# electronics_board.net
KiCad netlist of a schematic drawn in EAGLE
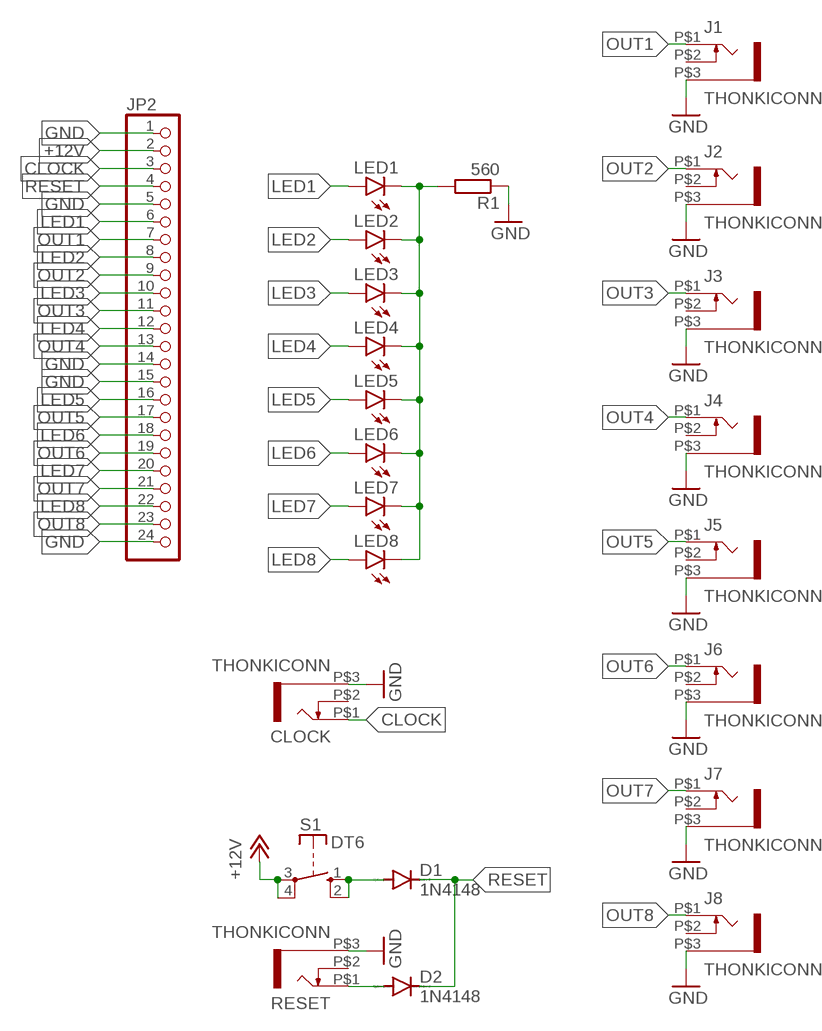
[diagram p0: schematic, sheet 1]

(export (version "E")
  (design (tool "Eeschema 10.0.6"))
  (components
    (comp (ref "CLOCK")
      (value "THONKICONN")
      (footprint "eagle-import:WQP-PJ301M-12_JACK")
      (libsource (lib "eagle-import") (part "WQP-PJ301M-12_JACK"))
    )
    (comp (ref "D1")
      (value "1N4148")
      (footprint "eagle-import:DO35-7")
      (libsource (lib "eagle-import") (part "1N4148DO35-7"))
    )
    (comp (ref "D2")
      (value "1N4148")
      (footprint "eagle-import:DO35-7")
      (libsource (lib "eagle-import") (part "1N4148DO35-7"))
    )
    (comp (ref "J1")
      (value "THONKICONN")
      (footprint "eagle-import:WQP-PJ301M-12_JACK")
      (libsource (lib "eagle-import") (part "WQP-PJ301M-12_JACK"))
    )
    (comp (ref "J2")
      (value "THONKICONN")
      (footprint "eagle-import:WQP-PJ301M-12_JACK")
      (libsource (lib "eagle-import") (part "WQP-PJ301M-12_JACK"))
    )
    (comp (ref "J3")
      (value "THONKICONN")
      (footprint "eagle-import:WQP-PJ301M-12_JACK")
      (libsource (lib "eagle-import") (part "WQP-PJ301M-12_JACK"))
    )
    (comp (ref "J4")
      (value "THONKICONN")
      (footprint "eagle-import:WQP-PJ301M-12_JACK")
      (libsource (lib "eagle-import") (part "WQP-PJ301M-12_JACK"))
    )
    (comp (ref "J5")
      (value "THONKICONN")
      (footprint "eagle-import:WQP-PJ301M-12_JACK")
      (libsource (lib "eagle-import") (part "WQP-PJ301M-12_JACK"))
    )
    (comp (ref "J6")
      (value "THONKICONN")
      (footprint "eagle-import:WQP-PJ301M-12_JACK")
      (libsource (lib "eagle-import") (part "WQP-PJ301M-12_JACK"))
    )
    (comp (ref "J7")
      (value "THONKICONN")
      (footprint "eagle-import:WQP-PJ301M-12_JACK")
      (libsource (lib "eagle-import") (part "WQP-PJ301M-12_JACK"))
    )
    (comp (ref "J8")
      (value "THONKICONN")
      (footprint "eagle-import:WQP-PJ301M-12_JACK")
      (libsource (lib "eagle-import") (part "WQP-PJ301M-12_JACK"))
    )
    (comp (ref "JP2")
      (value "PINHD-1X24")
      (footprint "eagle-import:1X24")
      (libsource (lib "eagle-import") (part "PINHD-1X24"))
    )
    (comp (ref "LED1")
      (value "LED")
      (footprint "eagle-import:LED_3MM")
      (fields (field (name "MF") "BROADCOM") (field (name "MPN") "HLMP-1700"))
      (libsource (lib "eagle-import") (part "LED"))
    )
    (comp (ref "LED2")
      (value "LED")
      (footprint "eagle-import:LED_3MM")
      (fields (field (name "MF") "BROADCOM") (field (name "MPN") "HLMP-1700"))
      (libsource (lib "eagle-import") (part "LED"))
    )
    (comp (ref "LED3")
      (value "LED")
      (footprint "eagle-import:LED_3MM")
      (fields (field (name "MF") "BROADCOM") (field (name "MPN") "HLMP-1700"))
      (libsource (lib "eagle-import") (part "LED"))
    )
    (comp (ref "LED4")
      (value "LED")
      (footprint "eagle-import:LED_3MM")
      (fields (field (name "MF") "BROADCOM") (field (name "MPN") "HLMP-1700"))
      (libsource (lib "eagle-import") (part "LED"))
    )
    (comp (ref "LED5")
      (value "LED")
      (footprint "eagle-import:LED_3MM")
      (fields (field (name "MF") "BROADCOM") (field (name "MPN") "HLMP-1700"))
      (libsource (lib "eagle-import") (part "LED"))
    )
    (comp (ref "LED6")
      (value "LED")
      (footprint "eagle-import:LED_3MM")
      (fields (field (name "MF") "BROADCOM") (field (name "MPN") "HLMP-1700"))
      (libsource (lib "eagle-import") (part "LED"))
    )
    (comp (ref "LED7")
      (value "LED")
      (footprint "eagle-import:LED_3MM")
      (fields (field (name "MF") "BROADCOM") (field (name "MPN") "HLMP-1700"))
      (libsource (lib "eagle-import") (part "LED"))
    )
    (comp (ref "LED8")
      (value "LED")
      (footprint "eagle-import:LED_3MM")
      (fields (field (name "MF") "BROADCOM") (field (name "MPN") "HLMP-1700"))
      (libsource (lib "eagle-import") (part "LED"))
    )
    (comp (ref "R1")
      (value "560")
      (footprint "eagle-import:0204_5")
      (fields (field (name "MF") "MULTICOMP PRO") (field (name "MPN") "MCF 0.25W 560R"))
      (libsource (lib "eagle-import") (part "R-EU_0204/5"))
    )
    (comp (ref "RESET")
      (value "THONKICONN")
      (footprint "eagle-import:WQP-PJ301M-12_JACK")
      (libsource (lib "eagle-import") (part "WQP-PJ301M-12_JACK"))
    )
    (comp (ref "S1")
      (value "DT6")
      (footprint "eagle-import:DT6")
      (libsource (lib "eagle-import") (part "DT6"))
    )
  )
  (nets
    (net (code "1") (name "+12V") (class "Default")
      (node (ref "JP2") (pin "2") (pinfunction "2_2") (pintype "passive"))
      (node (ref "S1") (pin "3") (pinfunction "P_3") (pintype "passive"))
      (node (ref "S1") (pin "4") (pinfunction "P_4") (pintype "passive"))
    )
    (net (code "2") (name "CLOCK") (class "Default")
      (node (ref "CLOCK") (pin "P$1") (pinfunction "2_P$1") (pintype "passive"))
      (node (ref "JP2") (pin "3") (pinfunction "3_3") (pintype "passive"))
    )
    (net (code "3") (name "GND") (class "Default")
      (node (ref "CLOCK") (pin "P$3") (pinfunction "1_P$3") (pintype "passive"))
      (node (ref "J1") (pin "P$3") (pinfunction "1_P$3") (pintype "passive"))
      (node (ref "J2") (pin "P$3") (pinfunction "1_P$3") (pintype "passive"))
      (node (ref "J3") (pin "P$3") (pinfunction "1_P$3") (pintype "passive"))
      (node (ref "J4") (pin "P$3") (pinfunction "1_P$3") (pintype "passive"))
      (node (ref "J5") (pin "P$3") (pinfunction "1_P$3") (pintype "passive"))
      (node (ref "J6") (pin "P$3") (pinfunction "1_P$3") (pintype "passive"))
      (node (ref "J7") (pin "P$3") (pinfunction "1_P$3") (pintype "passive"))
      (node (ref "J8") (pin "P$3") (pinfunction "1_P$3") (pintype "passive"))
      (node (ref "JP2") (pin "1") (pinfunction "1_1") (pintype "passive"))
      (node (ref "JP2") (pin "14") (pinfunction "14_14") (pintype "passive"))
      (node (ref "JP2") (pin "15") (pinfunction "15_15") (pintype "passive"))
      (node (ref "JP2") (pin "24") (pinfunction "24_24") (pintype "passive"))
      (node (ref "JP2") (pin "5") (pinfunction "5_5") (pintype "passive"))
      (node (ref "R1") (pin "1") (pinfunction "1_1") (pintype "passive"))
      (node (ref "RESET") (pin "P$3") (pinfunction "1_P$3") (pintype "passive"))
    )
    (net (code "4") (name "LED1") (class "Default")
      (node (ref "JP2") (pin "6") (pinfunction "6_6") (pintype "passive"))
      (node (ref "LED1") (pin "A") (pinfunction "A_A") (pintype "passive"))
    )
    (net (code "5") (name "LED2") (class "Default")
      (node (ref "JP2") (pin "8") (pinfunction "8_8") (pintype "passive"))
      (node (ref "LED2") (pin "A") (pinfunction "A_A") (pintype "passive"))
    )
    (net (code "6") (name "LED3") (class "Default")
      (node (ref "JP2") (pin "10") (pinfunction "10_10") (pintype "passive"))
      (node (ref "LED3") (pin "A") (pinfunction "A_A") (pintype "passive"))
    )
    (net (code "7") (name "LED4") (class "Default")
      (node (ref "JP2") (pin "12") (pinfunction "12_12") (pintype "passive"))
      (node (ref "LED4") (pin "A") (pinfunction "A_A") (pintype "passive"))
    )
    (net (code "8") (name "LED5") (class "Default")
      (node (ref "JP2") (pin "16") (pinfunction "16_16") (pintype "passive"))
      (node (ref "LED5") (pin "A") (pinfunction "A_A") (pintype "passive"))
    )
    (net (code "9") (name "LED6") (class "Default")
      (node (ref "JP2") (pin "18") (pinfunction "18_18") (pintype "passive"))
      (node (ref "LED6") (pin "A") (pinfunction "A_A") (pintype "passive"))
    )
    (net (code "10") (name "LED7") (class "Default")
      (node (ref "JP2") (pin "20") (pinfunction "20_20") (pintype "passive"))
      (node (ref "LED7") (pin "A") (pinfunction "A_A") (pintype "passive"))
    )
    (net (code "11") (name "LED8") (class "Default")
      (node (ref "JP2") (pin "22") (pinfunction "22_22") (pintype "passive"))
      (node (ref "LED8") (pin "A") (pinfunction "A_A") (pintype "passive"))
    )
    (net (code "12") (name "Net-(D1-PadA)") (class "Default")
      (node (ref "D1") (pin "A") (pinfunction "A_A") (pintype "passive"))
      (node (ref "S1") (pin "1") (pinfunction "S_1") (pintype "passive"))
      (node (ref "S1") (pin "2") (pinfunction "S_2") (pintype "passive"))
    )
    (net (code "13") (name "Net-(LED1-C)") (class "Default")
      (node (ref "LED1") (pin "K") (pinfunction "C_K") (pintype "passive"))
      (node (ref "LED2") (pin "K") (pinfunction "C_K") (pintype "passive"))
      (node (ref "LED3") (pin "K") (pinfunction "C_K") (pintype "passive"))
      (node (ref "LED4") (pin "K") (pinfunction "C_K") (pintype "passive"))
      (node (ref "LED5") (pin "K") (pinfunction "C_K") (pintype "passive"))
      (node (ref "LED6") (pin "K") (pinfunction "C_K") (pintype "passive"))
      (node (ref "LED7") (pin "K") (pinfunction "C_K") (pintype "passive"))
      (node (ref "LED8") (pin "K") (pinfunction "C_K") (pintype "passive"))
      (node (ref "R1") (pin "2") (pinfunction "2_2") (pintype "passive"))
    )
    (net (code "14") (name "Net-(RESET-2)") (class "Default")
      (node (ref "D2") (pin "A") (pinfunction "A_A") (pintype "passive"))
      (node (ref "RESET") (pin "P$1") (pinfunction "2_P$1") (pintype "passive"))
    )
    (net (code "15") (name "OUT1") (class "Default")
      (node (ref "J1") (pin "P$1") (pinfunction "2_P$1") (pintype "passive"))
      (node (ref "JP2") (pin "7") (pinfunction "7_7") (pintype "passive"))
    )
    (net (code "16") (name "OUT2") (class "Default")
      (node (ref "J2") (pin "P$1") (pinfunction "2_P$1") (pintype "passive"))
      (node (ref "JP2") (pin "9") (pinfunction "9_9") (pintype "passive"))
    )
    (net (code "17") (name "OUT3") (class "Default")
      (node (ref "J3") (pin "P$1") (pinfunction "2_P$1") (pintype "passive"))
      (node (ref "JP2") (pin "11") (pinfunction "11_11") (pintype "passive"))
    )
    (net (code "18") (name "OUT4") (class "Default")
      (node (ref "J4") (pin "P$1") (pinfunction "2_P$1") (pintype "passive"))
      (node (ref "JP2") (pin "13") (pinfunction "13_13") (pintype "passive"))
    )
    (net (code "19") (name "OUT5") (class "Default")
      (node (ref "J5") (pin "P$1") (pinfunction "2_P$1") (pintype "passive"))
      (node (ref "JP2") (pin "17") (pinfunction "17_17") (pintype "passive"))
    )
    (net (code "20") (name "OUT6") (class "Default")
      (node (ref "J6") (pin "P$1") (pinfunction "2_P$1") (pintype "passive"))
      (node (ref "JP2") (pin "19") (pinfunction "19_19") (pintype "passive"))
    )
    (net (code "21") (name "OUT7") (class "Default")
      (node (ref "J7") (pin "P$1") (pinfunction "2_P$1") (pintype "passive"))
      (node (ref "JP2") (pin "21") (pinfunction "21_21") (pintype "passive"))
    )
    (net (code "22") (name "OUT8") (class "Default")
      (node (ref "J8") (pin "P$1") (pinfunction "2_P$1") (pintype "passive"))
      (node (ref "JP2") (pin "23") (pinfunction "23_23") (pintype "passive"))
    )
    (net (code "23") (name "RESET") (class "Default")
      (node (ref "D1") (pin "C") (pinfunction "C_C") (pintype "passive"))
      (node (ref "D2") (pin "C") (pinfunction "C_C") (pintype "passive"))
      (node (ref "JP2") (pin "4") (pinfunction "4_4") (pintype "passive"))
    )
    (net (code "24") (name "unconnected-(CLOCK-3-PadP$2)") (class "Default")
      (node (ref "CLOCK") (pin "P$2") (pinfunction "3_P$2") (pintype "passive"))
    )
    (net (code "25") (name "unconnected-(J1-3-PadP$2)") (class "Default")
      (node (ref "J1") (pin "P$2") (pinfunction "3_P$2") (pintype "passive"))
    )
    (net (code "26") (name "unconnected-(J2-3-PadP$2)") (class "Default")
      (node (ref "J2") (pin "P$2") (pinfunction "3_P$2") (pintype "passive"))
    )
    (net (code "27") (name "unconnected-(J3-3-PadP$2)") (class "Default")
      (node (ref "J3") (pin "P$2") (pinfunction "3_P$2") (pintype "passive"))
    )
    (net (code "28") (name "unconnected-(J4-3-PadP$2)") (class "Default")
      (node (ref "J4") (pin "P$2") (pinfunction "3_P$2") (pintype "passive"))
    )
    (net (code "29") (name "unconnected-(J5-3-PadP$2)") (class "Default")
      (node (ref "J5") (pin "P$2") (pinfunction "3_P$2") (pintype "passive"))
    )
    (net (code "30") (name "unconnected-(J6-3-PadP$2)") (class "Default")
      (node (ref "J6") (pin "P$2") (pinfunction "3_P$2") (pintype "passive"))
    )
    (net (code "31") (name "unconnected-(J7-3-PadP$2)") (class "Default")
      (node (ref "J7") (pin "P$2") (pinfunction "3_P$2") (pintype "passive"))
    )
    (net (code "32") (name "unconnected-(J8-3-PadP$2)") (class "Default")
      (node (ref "J8") (pin "P$2") (pinfunction "3_P$2") (pintype "passive"))
    )
    (net (code "33") (name "unconnected-(RESET-3-PadP$2)") (class "Default")
      (node (ref "RESET") (pin "P$2") (pinfunction "3_P$2") (pintype "passive"))
    )
  )
)
